# main_2.net
KiCad netlist of a schematic drawn in EAGLE
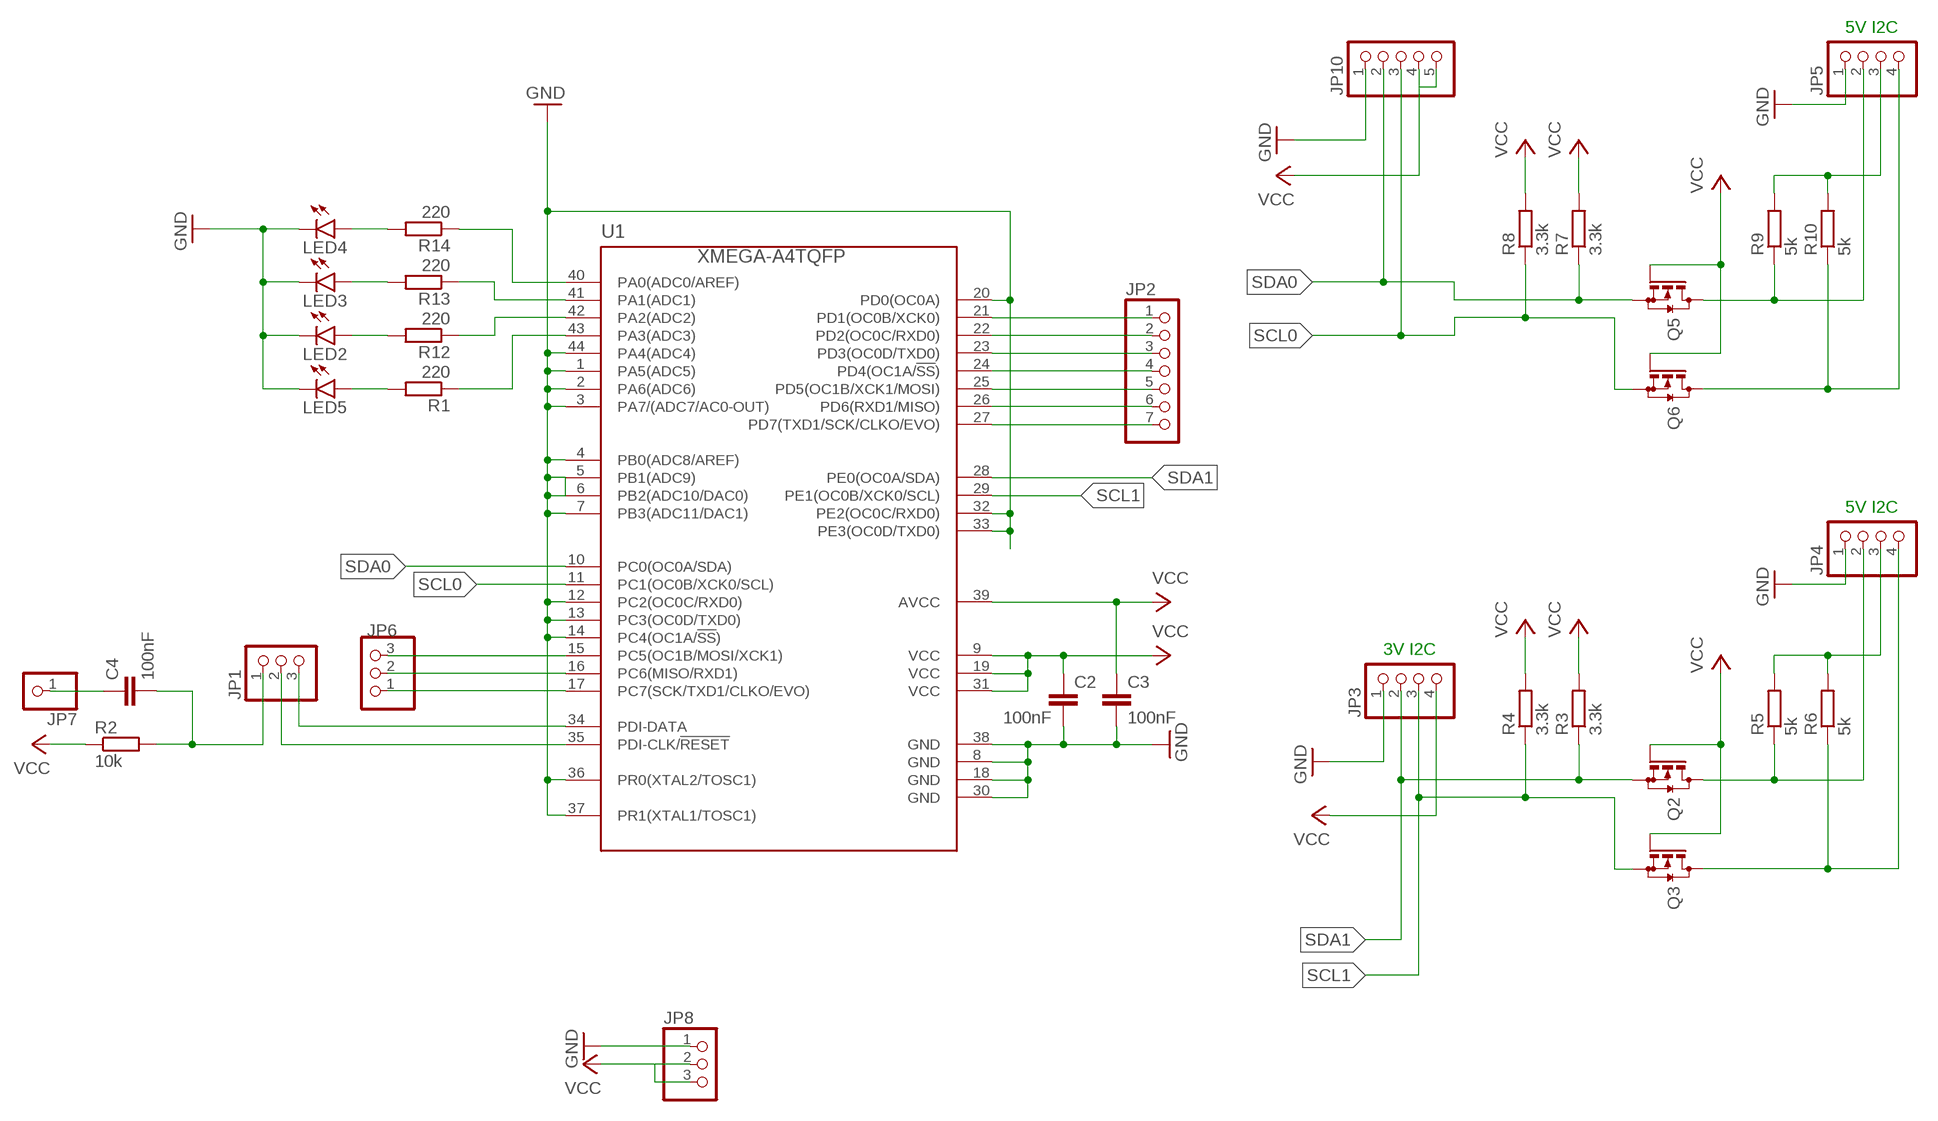
[diagram p0: schematic, sheet 1]

(export (version "E")
  (design (tool "Eeschema 10.0.6"))
  (components
    (comp (ref "C2")
      (value "100nF")
      (footprint "eagle-import:C0805")
      (libsource (lib "eagle-import") (part "C"))
    )
    (comp (ref "C3")
      (value "100nF")
      (footprint "eagle-import:C0805")
      (libsource (lib "eagle-import") (part "C"))
    )
    (comp (ref "C4")
      (value "100nF")
      (footprint "eagle-import:C0805")
      (libsource (lib "eagle-import") (part "C"))
    )
    (comp (ref "JP1")
      (value "PINHD-1X3")
      (footprint "eagle-import:1X03")
      (libsource (lib "eagle-import") (part "PINHD-1X3"))
    )
    (comp (ref "JP2")
      (value "PINHD-1X7")
      (footprint "eagle-import:1X07")
      (libsource (lib "eagle-import") (part "PINHD-1X7"))
    )
    (comp (ref "JP3")
      (value "PINHD-1X4")
      (footprint "eagle-import:1X04")
      (libsource (lib "eagle-import") (part "PINHD-1X4"))
    )
    (comp (ref "JP4")
      (value "PINHD-1X4")
      (footprint "eagle-import:1X04")
      (libsource (lib "eagle-import") (part "PINHD-1X4"))
    )
    (comp (ref "JP5")
      (value "PINHD-1X4")
      (footprint "eagle-import:1X04")
      (libsource (lib "eagle-import") (part "PINHD-1X4"))
    )
    (comp (ref "JP6")
      (value "PINHD-1X3")
      (footprint "eagle-import:1X03")
      (libsource (lib "eagle-import") (part "PINHD-1X3"))
    )
    (comp (ref "JP7")
      (value "PINHD-1X1")
      (footprint "eagle-import:1X01")
      (libsource (lib "eagle-import") (part "PINHD-1X1"))
    )
    (comp (ref "JP8")
      (value "PINHD-1X3")
      (footprint "eagle-import:1X03")
      (libsource (lib "eagle-import") (part "PINHD-1X3"))
    )
    (comp (ref "JP10")
      (value "PINHD-1X5")
      (footprint "eagle-import:1X05")
      (libsource (lib "eagle-import") (part "PINHD-1X5"))
    )
    (comp (ref "LED2")
      (value "LED1206")
      (footprint "eagle-import:LED-1206")
      (libsource (lib "eagle-import") (part "LED1206"))
    )
    (comp (ref "LED3")
      (value "LED1206")
      (footprint "eagle-import:LED-1206")
      (libsource (lib "eagle-import") (part "LED1206"))
    )
    (comp (ref "LED4")
      (value "LED1206")
      (footprint "eagle-import:LED-1206")
      (libsource (lib "eagle-import") (part "LED1206"))
    )
    (comp (ref "LED5")
      (value "LED1206")
      (footprint "eagle-import:LED-1206")
      (libsource (lib "eagle-import") (part "LED1206"))
    )
    (comp (ref "Q2")
      (value "BSS123")
      (footprint "eagle-import:SOT23")
      (libsource (lib "eagle-import") (part "BSS123"))
    )
    (comp (ref "Q3")
      (value "BSS123")
      (footprint "eagle-import:SOT23")
      (libsource (lib "eagle-import") (part "BSS123"))
    )
    (comp (ref "Q5")
      (value "BSS123")
      (footprint "eagle-import:SOT23")
      (libsource (lib "eagle-import") (part "BSS123"))
    )
    (comp (ref "Q6")
      (value "BSS123")
      (footprint "eagle-import:SOT23")
      (libsource (lib "eagle-import") (part "BSS123"))
    )
    (comp (ref "R1")
      (value "220")
      (footprint "eagle-import:R0805")
      (libsource (lib "eagle-import") (part "R"))
    )
    (comp (ref "R2")
      (value "10k")
      (footprint "eagle-import:R0805")
      (libsource (lib "eagle-import") (part "R"))
    )
    (comp (ref "R3")
      (value "3.3k")
      (footprint "eagle-import:R0805")
      (libsource (lib "eagle-import") (part "R"))
    )
    (comp (ref "R4")
      (value "3.3k")
      (footprint "eagle-import:R0805")
      (libsource (lib "eagle-import") (part "R"))
    )
    (comp (ref "R5")
      (value "5k")
      (footprint "eagle-import:R0805")
      (libsource (lib "eagle-import") (part "R"))
    )
    (comp (ref "R6")
      (value "5k")
      (footprint "eagle-import:R0805")
      (libsource (lib "eagle-import") (part "R"))
    )
    (comp (ref "R7")
      (value "3.3k")
      (footprint "eagle-import:R0805")
      (libsource (lib "eagle-import") (part "R"))
    )
    (comp (ref "R8")
      (value "3.3k")
      (footprint "eagle-import:R0805")
      (libsource (lib "eagle-import") (part "R"))
    )
    (comp (ref "R9")
      (value "5k")
      (footprint "eagle-import:R0805")
      (libsource (lib "eagle-import") (part "R"))
    )
    (comp (ref "R10")
      (value "5k")
      (footprint "eagle-import:R0805")
      (libsource (lib "eagle-import") (part "R"))
    )
    (comp (ref "R12")
      (value "220")
      (footprint "eagle-import:R0805")
      (libsource (lib "eagle-import") (part "R"))
    )
    (comp (ref "R13")
      (value "220")
      (footprint "eagle-import:R0805")
      (libsource (lib "eagle-import") (part "R"))
    )
    (comp (ref "R14")
      (value "220")
      (footprint "eagle-import:R0805")
      (libsource (lib "eagle-import") (part "R"))
    )
    (comp (ref "U1")
      (value "XMEGA-A4TQFP")
      (footprint "eagle-import:TQFP44")
      (libsource (lib "eagle-import") (part "XMEGA-A4TQFP"))
    )
  )
  (nets
    (net (code "1") (name "GND") (class "Default")
      (node (ref "C2") (pin "2") (pinfunction "2_2") (pintype "passive"))
      (node (ref "C3") (pin "2") (pinfunction "2_2") (pintype "passive"))
      (node (ref "JP10") (pin "1") (pinfunction "1_1") (pintype "passive"))
      (node (ref "JP3") (pin "1") (pinfunction "1_1") (pintype "passive"))
      (node (ref "JP4") (pin "1") (pinfunction "1_1") (pintype "passive"))
      (node (ref "JP5") (pin "1") (pinfunction "1_1") (pintype "passive"))
      (node (ref "JP8") (pin "1") (pinfunction "1_1") (pintype "passive"))
      (node (ref "LED2") (pin "C") (pinfunction "C_C") (pintype "passive"))
      (node (ref "LED3") (pin "C") (pinfunction "C_C") (pintype "passive"))
      (node (ref "LED4") (pin "C") (pinfunction "C_C") (pintype "passive"))
      (node (ref "LED5") (pin "C") (pinfunction "C_C") (pintype "passive"))
      (node (ref "U1") (pin "1") (pinfunction "PA5(ADC5)_1") (pintype "bidirectional"))
      (node (ref "U1") (pin "12") (pinfunction "PC2(OC0C/RXD0)_12") (pintype "bidirectional"))
      (node (ref "U1") (pin "13") (pinfunction "PC3(OC0D/TXD0)_13") (pintype "bidirectional"))
      (node (ref "U1") (pin "14") (pinfunction "PC4(OC1A/~{SS})_14") (pintype "bidirectional"))
      (node (ref "U1") (pin "18") (pinfunction "GND_18") (pintype "power_in"))
      (node (ref "U1") (pin "2") (pinfunction "PA6(ADC6)_2") (pintype "bidirectional"))
      (node (ref "U1") (pin "20") (pinfunction "PD0(OC0A)_20") (pintype "bidirectional"))
      (node (ref "U1") (pin "3") (pinfunction "PA7/(ADC7/AC0-OUT)_3") (pintype "bidirectional"))
      (node (ref "U1") (pin "30") (pinfunction "GND_30") (pintype "power_in"))
      (node (ref "U1") (pin "32") (pinfunction "PE2(OC0C/RXD0)_32") (pintype "bidirectional"))
      (node (ref "U1") (pin "33") (pinfunction "PE3(OC0D/TXD0)_33") (pintype "bidirectional"))
      (node (ref "U1") (pin "36") (pinfunction "PR0(XTAL2/TOSC1)_36") (pintype "bidirectional"))
      (node (ref "U1") (pin "37") (pinfunction "PR1(XTAL1/TOSC1)_37") (pintype "bidirectional"))
      (node (ref "U1") (pin "38") (pinfunction "GND_38") (pintype "power_in"))
      (node (ref "U1") (pin "4") (pinfunction "PB0(ADC8/AREF)_4") (pintype "bidirectional"))
      (node (ref "U1") (pin "44") (pinfunction "PA4(ADC4)_44") (pintype "bidirectional"))
      (node (ref "U1") (pin "5") (pinfunction "PB1(ADC9)_5") (pintype "bidirectional"))
      (node (ref "U1") (pin "6") (pinfunction "PB2(ADC10/DAC0)_6") (pintype "bidirectional"))
      (node (ref "U1") (pin "7") (pinfunction "PB3(ADC11/DAC1)_7") (pintype "bidirectional"))
      (node (ref "U1") (pin "8") (pinfunction "GND_8") (pintype "power_in"))
    )
    (net (code "2") (name "Net-(C4-Pad1)") (class "Default")
      (node (ref "C4") (pin "1") (pinfunction "1_1") (pintype "passive"))
      (node (ref "JP7") (pin "1") (pinfunction "1_1") (pintype "passive"))
    )
    (net (code "3") (name "Net-(C4-Pad2)") (class "Default")
      (node (ref "C4") (pin "2") (pinfunction "2_2") (pintype "passive"))
      (node (ref "JP1") (pin "1") (pinfunction "1_1") (pintype "passive"))
      (node (ref "R2") (pin "2") (pinfunction "2_2") (pintype "passive"))
    )
    (net (code "4") (name "Net-(JP4-Pad3)") (class "Default")
      (node (ref "JP4") (pin "3") (pinfunction "3_3") (pintype "passive"))
      (node (ref "R5") (pin "2") (pinfunction "2_2") (pintype "passive"))
      (node (ref "R6") (pin "2") (pinfunction "2_2") (pintype "passive"))
    )
    (net (code "5") (name "Net-(JP5-Pad3)") (class "Default")
      (node (ref "JP5") (pin "3") (pinfunction "3_3") (pintype "passive"))
      (node (ref "R10") (pin "2") (pinfunction "2_2") (pintype "passive"))
      (node (ref "R9") (pin "2") (pinfunction "2_2") (pintype "passive"))
    )
    (net (code "6") (name "Net-(LED2-PadA)") (class "Default")
      (node (ref "LED2") (pin "A") (pinfunction "A_A") (pintype "passive"))
      (node (ref "R12") (pin "2") (pinfunction "2_2") (pintype "passive"))
    )
    (net (code "7") (name "Net-(LED3-PadA)") (class "Default")
      (node (ref "LED3") (pin "A") (pinfunction "A_A") (pintype "passive"))
      (node (ref "R13") (pin "2") (pinfunction "2_2") (pintype "passive"))
    )
    (net (code "8") (name "Net-(LED4-PadA)") (class "Default")
      (node (ref "LED4") (pin "A") (pinfunction "A_A") (pintype "passive"))
      (node (ref "R14") (pin "2") (pinfunction "2_2") (pintype "passive"))
    )
    (net (code "9") (name "Net-(LED5-PadA)") (class "Default")
      (node (ref "LED5") (pin "A") (pinfunction "A_A") (pintype "passive"))
      (node (ref "R1") (pin "2") (pinfunction "2_2") (pintype "passive"))
    )
    (net (code "10") (name "Net-(Q2-D)") (class "Default")
      (node (ref "JP4") (pin "2") (pinfunction "2_2") (pintype "passive"))
      (node (ref "Q2") (pin "3") (pinfunction "D_3") (pintype "passive"))
      (node (ref "R5") (pin "1") (pinfunction "1_1") (pintype "passive"))
    )
    (net (code "11") (name "Net-(Q3-D)") (class "Default")
      (node (ref "JP4") (pin "4") (pinfunction "4_4") (pintype "passive"))
      (node (ref "Q3") (pin "3") (pinfunction "D_3") (pintype "passive"))
      (node (ref "R6") (pin "1") (pinfunction "1_1") (pintype "passive"))
    )
    (net (code "12") (name "Net-(Q5-D)") (class "Default")
      (node (ref "JP5") (pin "2") (pinfunction "2_2") (pintype "passive"))
      (node (ref "Q5") (pin "3") (pinfunction "D_3") (pintype "passive"))
      (node (ref "R9") (pin "1") (pinfunction "1_1") (pintype "passive"))
    )
    (net (code "13") (name "Net-(Q6-D)") (class "Default")
      (node (ref "JP5") (pin "4") (pinfunction "4_4") (pintype "passive"))
      (node (ref "Q6") (pin "3") (pinfunction "D_3") (pintype "passive"))
      (node (ref "R10") (pin "1") (pinfunction "1_1") (pintype "passive"))
    )
    (net (code "14") (name "Net-(U1-PA0(ADC0{slash}AREF))") (class "Default")
      (node (ref "R14") (pin "1") (pinfunction "1_1") (pintype "passive"))
      (node (ref "U1") (pin "40") (pinfunction "PA0(ADC0/AREF)_40") (pintype "bidirectional"))
    )
    (net (code "15") (name "Net-(U1-PA1(ADC1))") (class "Default")
      (node (ref "R13") (pin "1") (pinfunction "1_1") (pintype "passive"))
      (node (ref "U1") (pin "41") (pinfunction "PA1(ADC1)_41") (pintype "bidirectional"))
    )
    (net (code "16") (name "Net-(U1-PA2(ADC2))") (class "Default")
      (node (ref "R12") (pin "1") (pinfunction "1_1") (pintype "passive"))
      (node (ref "U1") (pin "42") (pinfunction "PA2(ADC2)_42") (pintype "bidirectional"))
    )
    (net (code "17") (name "Net-(U1-PA3(ADC3))") (class "Default")
      (node (ref "R1") (pin "1") (pinfunction "1_1") (pintype "passive"))
      (node (ref "U1") (pin "43") (pinfunction "PA3(ADC3)_43") (pintype "bidirectional"))
    )
    (net (code "18") (name "Net-(U1-PC5(OC1B{slash}MOSI{slash}XCK1))") (class "Default")
      (node (ref "JP6") (pin "3") (pinfunction "3_3") (pintype "passive"))
      (node (ref "U1") (pin "15") (pinfunction "PC5(OC1B/MOSI/XCK1)_15") (pintype "bidirectional"))
    )
    (net (code "19") (name "Net-(U1-PC6(MISO{slash}RXD1))") (class "Default")
      (node (ref "JP6") (pin "2") (pinfunction "2_2") (pintype "passive"))
      (node (ref "U1") (pin "16") (pinfunction "PC6(MISO/RXD1)_16") (pintype "bidirectional"))
    )
    (net (code "20") (name "Net-(U1-PC7(SCK{slash}TXD1{slash}CLKO{slash}EVO))") (class "Default")
      (node (ref "JP6") (pin "1") (pinfunction "1_1") (pintype "passive"))
      (node (ref "U1") (pin "17") (pinfunction "PC7(SCK/TXD1/CLKO/EVO)_17") (pintype "bidirectional"))
    )
    (net (code "21") (name "Net-(U1-PD1(OC0B{slash}XCK0))") (class "Default")
      (node (ref "JP2") (pin "1") (pinfunction "1_1") (pintype "passive"))
      (node (ref "U1") (pin "21") (pinfunction "PD1(OC0B/XCK0)_21") (pintype "bidirectional"))
    )
    (net (code "22") (name "Net-(U1-PD2(OC0C{slash}RXD0))") (class "Default")
      (node (ref "JP2") (pin "2") (pinfunction "2_2") (pintype "passive"))
      (node (ref "U1") (pin "22") (pinfunction "PD2(OC0C/RXD0)_22") (pintype "bidirectional"))
    )
    (net (code "23") (name "Net-(U1-PD3(OC0D{slash}TXD0))") (class "Default")
      (node (ref "JP2") (pin "3") (pinfunction "3_3") (pintype "passive"))
      (node (ref "U1") (pin "23") (pinfunction "PD3(OC0D/TXD0)_23") (pintype "bidirectional"))
    )
    (net (code "24") (name "Net-(U1-PD4(OC1A{slash}~{SS}))") (class "Default")
      (node (ref "JP2") (pin "4") (pinfunction "4_4") (pintype "passive"))
      (node (ref "U1") (pin "24") (pinfunction "PD4(OC1A/~{SS})_24") (pintype "bidirectional"))
    )
    (net (code "25") (name "Net-(U1-PD5(OC1B{slash}XCK1{slash}MOSI))") (class "Default")
      (node (ref "JP2") (pin "5") (pinfunction "5_5") (pintype "passive"))
      (node (ref "U1") (pin "25") (pinfunction "PD5(OC1B/XCK1/MOSI)_25") (pintype "bidirectional"))
    )
    (net (code "26") (name "Net-(U1-PD6(RXD1{slash}MISO))") (class "Default")
      (node (ref "JP2") (pin "6") (pinfunction "6_6") (pintype "passive"))
      (node (ref "U1") (pin "26") (pinfunction "PD6(RXD1/MISO)_26") (pintype "bidirectional"))
    )
    (net (code "27") (name "Net-(U1-PD7(TXD1{slash}SCK{slash}CLKO{slash}EVO))") (class "Default")
      (node (ref "JP2") (pin "7") (pinfunction "7_7") (pintype "passive"))
      (node (ref "U1") (pin "27") (pinfunction "PD7(TXD1/SCK/CLKO/EVO)_27") (pintype "bidirectional"))
    )
    (net (code "28") (name "Net-(U1-PDI-CLK{slash}~{RESET})") (class "Default")
      (node (ref "JP1") (pin "2") (pinfunction "2_2") (pintype "passive"))
      (node (ref "U1") (pin "35") (pinfunction "PDI-CLK/~{RESET}_35") (pintype "input"))
    )
    (net (code "29") (name "Net-(U1-PDI-DATA)") (class "Default")
      (node (ref "JP1") (pin "3") (pinfunction "3_3") (pintype "passive"))
      (node (ref "U1") (pin "34") (pinfunction "PDI-DATA_34") (pintype "bidirectional"))
    )
    (net (code "30") (name "SCL0") (class "Default")
      (node (ref "JP10") (pin "3") (pinfunction "3_3") (pintype "passive"))
      (node (ref "Q6") (pin "2") (pinfunction "S_2") (pintype "passive"))
      (node (ref "R8") (pin "1") (pinfunction "1_1") (pintype "passive"))
      (node (ref "U1") (pin "11") (pinfunction "PC1(OC0B/XCK0/SCL)_11") (pintype "bidirectional"))
    )
    (net (code "31") (name "SCL1") (class "Default")
      (node (ref "JP3") (pin "3") (pinfunction "3_3") (pintype "passive"))
      (node (ref "Q3") (pin "2") (pinfunction "S_2") (pintype "passive"))
      (node (ref "R4") (pin "1") (pinfunction "1_1") (pintype "passive"))
      (node (ref "U1") (pin "29") (pinfunction "PE1(OC0B/XCK0/SCL)_29") (pintype "bidirectional"))
    )
    (net (code "32") (name "SDA0") (class "Default")
      (node (ref "JP10") (pin "2") (pinfunction "2_2") (pintype "passive"))
      (node (ref "Q5") (pin "2") (pinfunction "S_2") (pintype "passive"))
      (node (ref "R7") (pin "1") (pinfunction "1_1") (pintype "passive"))
      (node (ref "U1") (pin "10") (pinfunction "PC0(OC0A/SDA)_10") (pintype "bidirectional"))
    )
    (net (code "33") (name "SDA1") (class "Default")
      (node (ref "JP3") (pin "2") (pinfunction "2_2") (pintype "passive"))
      (node (ref "Q2") (pin "2") (pinfunction "S_2") (pintype "passive"))
      (node (ref "R3") (pin "1") (pinfunction "1_1") (pintype "passive"))
      (node (ref "U1") (pin "28") (pinfunction "PE0(OC0A/SDA)_28") (pintype "bidirectional"))
    )
    (net (code "34") (name "VCC") (class "Default")
      (node (ref "C2") (pin "1") (pinfunction "1_1") (pintype "passive"))
      (node (ref "C3") (pin "1") (pinfunction "1_1") (pintype "passive"))
      (node (ref "JP10") (pin "4") (pinfunction "4_4") (pintype "passive"))
      (node (ref "JP10") (pin "5") (pinfunction "5_5") (pintype "passive"))
      (node (ref "JP3") (pin "4") (pinfunction "4_4") (pintype "passive"))
      (node (ref "JP8") (pin "2") (pinfunction "2_2") (pintype "passive"))
      (node (ref "JP8") (pin "3") (pinfunction "3_3") (pintype "passive"))
      (node (ref "Q2") (pin "1") (pinfunction "G_1") (pintype "passive"))
      (node (ref "Q3") (pin "1") (pinfunction "G_1") (pintype "passive"))
      (node (ref "Q5") (pin "1") (pinfunction "G_1") (pintype "passive"))
      (node (ref "Q6") (pin "1") (pinfunction "G_1") (pintype "passive"))
      (node (ref "R2") (pin "1") (pinfunction "1_1") (pintype "passive"))
      (node (ref "R3") (pin "2") (pinfunction "2_2") (pintype "passive"))
      (node (ref "R4") (pin "2") (pinfunction "2_2") (pintype "passive"))
      (node (ref "R7") (pin "2") (pinfunction "2_2") (pintype "passive"))
      (node (ref "R8") (pin "2") (pinfunction "2_2") (pintype "passive"))
      (node (ref "U1") (pin "19") (pinfunction "VCC_19") (pintype "power_in"))
      (node (ref "U1") (pin "31") (pinfunction "VCC_31") (pintype "power_in"))
      (node (ref "U1") (pin "39") (pinfunction "AVCC_39") (pintype "power_in"))
      (node (ref "U1") (pin "9") (pinfunction "VCC_9") (pintype "power_in"))
    )
  )
)
